# SparkFun_Transparent_Graphical_OLED_Brea.net
KiCad netlist of a schematic drawn in EAGLE
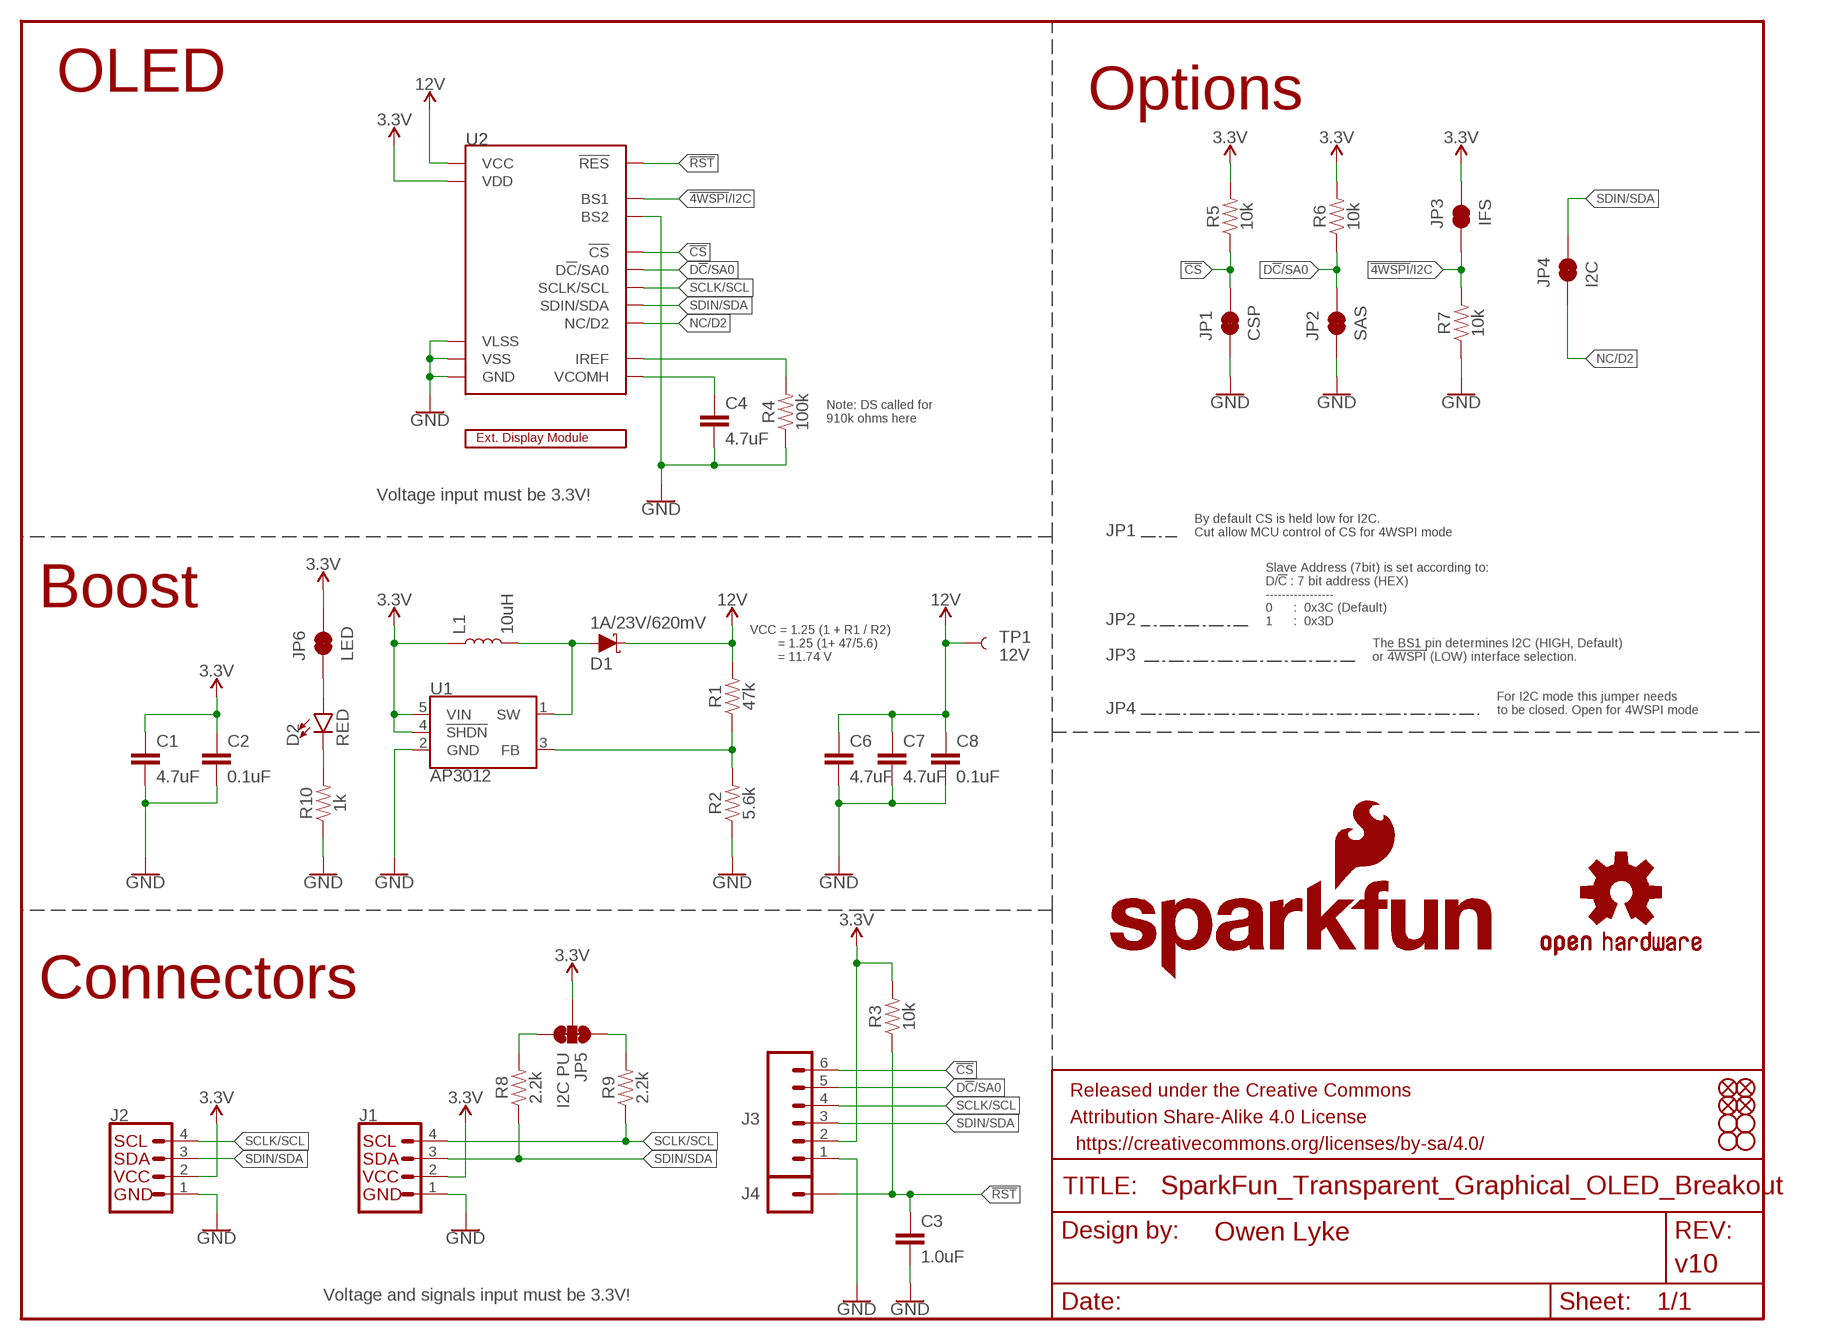
[diagram p0: schematic, sheet 1]

(export (version "E")
  (design (tool "Eeschema 10.0.6"))
  (components
    (comp (ref "C1")
      (value "4.7uF")
      (footprint "eagle-import:0603")
      (libsource (lib "eagle-import") (part "4.7UF-0603-35V-(20%)"))
    )
    (comp (ref "C2")
      (value "0.1uF")
      (footprint "eagle-import:0603")
      (libsource (lib "eagle-import") (part "0.1UF-0603-100V-10%"))
    )
    (comp (ref "C3")
      (value "1.0uF")
      (footprint "eagle-import:0603")
      (libsource (lib "eagle-import") (part "1.0UF-0603-16V-10%-X7R"))
    )
    (comp (ref "C4")
      (value "4.7uF")
      (footprint "eagle-import:0603")
      (libsource (lib "eagle-import") (part "4.7UF-0603-35V-(20%)"))
    )
    (comp (ref "C6")
      (value "4.7uF")
      (footprint "eagle-import:0603")
      (libsource (lib "eagle-import") (part "4.7UF-0603-35V-(20%)"))
    )
    (comp (ref "C7")
      (value "4.7uF")
      (footprint "eagle-import:0603")
      (libsource (lib "eagle-import") (part "4.7UF-0603-35V-(20%)"))
    )
    (comp (ref "C8")
      (value "0.1uF")
      (footprint "eagle-import:0603")
      (libsource (lib "eagle-import") (part "0.1UF-0603-100V-10%"))
    )
    (comp (ref "D1")
      (value "1A/23V/620mV")
      (footprint "eagle-import:SOD-323")
      (libsource (lib "eagle-import") (part "DIODE-SCHOTTKY-BAT20J"))
    )
    (comp (ref "D2")
      (value "RED")
      (footprint "eagle-import:LED-0603")
      (libsource (lib "eagle-import") (part "LED-RED0603"))
    )
    (comp (ref "FD1")
      (value "FIDUCIAL1X2")
      (footprint "eagle-import:FIDUCIAL-1X2")
      (libsource (lib "eagle-import") (part "FIDUCIAL1X2"))
    )
    (comp (ref "FD2")
      (value "FIDUCIAL1X2")
      (footprint "eagle-import:FIDUCIAL-1X2")
      (libsource (lib "eagle-import") (part "FIDUCIAL1X2"))
    )
    (comp (ref "FD3")
      (value "FIDUCIAL1X2")
      (footprint "eagle-import:FIDUCIAL-1X2")
      (libsource (lib "eagle-import") (part "FIDUCIAL1X2"))
    )
    (comp (ref "FD4")
      (value "FIDUCIAL1X2")
      (footprint "eagle-import:FIDUCIAL-1X2")
      (libsource (lib "eagle-import") (part "FIDUCIAL1X2"))
    )
    (comp (ref "FRAME1")
      (value "FRAME-LETTER")
      (footprint "eagle-import:CREATIVE_COMMONS")
      (fields (field (name "DESIGNER") "Owen Lyke") (field (name "REV") "v10"))
      (libsource (lib "eagle-import") (part "FRAME-LETTER"))
    )
    (comp (ref "H1")
      (value "STAND-OFF")
      (footprint "eagle-import:STAND-OFF")
      (libsource (lib "eagle-import") (part "STAND-OFF"))
    )
    (comp (ref "H2")
      (value "STAND-OFF")
      (footprint "eagle-import:STAND-OFF")
      (libsource (lib "eagle-import") (part "STAND-OFF"))
    )
    (comp (ref "H3")
      (value "STAND-OFF")
      (footprint "eagle-import:STAND-OFF")
      (libsource (lib "eagle-import") (part "STAND-OFF"))
    )
    (comp (ref "H4")
      (value "STAND-OFF")
      (footprint "eagle-import:STAND-OFF")
      (libsource (lib "eagle-import") (part "STAND-OFF"))
    )
    (comp (ref "J1")
      (value "QWIIC_CONNECTORJS-1MM")
      (footprint "eagle-import:JST04_1MM_RA")
      (libsource (lib "eagle-import") (part "QWIIC_CONNECTORJS-1MM"))
    )
    (comp (ref "J2")
      (value "QWIIC_CONNECTORJS-1MM")
      (footprint "eagle-import:JST04_1MM_RA")
      (libsource (lib "eagle-import") (part "QWIIC_CONNECTORJS-1MM"))
    )
    (comp (ref "J3")
      (value "CONN_06NO_SILK_NO_POP")
      (footprint "eagle-import:1X06_NO_SILK")
      (libsource (lib "eagle-import") (part "CONN_06NO_SILK_NO_POP"))
    )
    (comp (ref "J4")
      (value "CONN_01PTH_NO_SILK_YES_STOP")
      (footprint "eagle-import:1X01_NO_SILK")
      (libsource (lib "eagle-import") (part "CONN_01PTH_NO_SILK_YES_STOP"))
    )
    (comp (ref "JP1")
      (value "CSP")
      (footprint "eagle-import:SMT-JUMPER_2_NC_TRACE_SILK")
      (libsource (lib "eagle-import") (part "JUMPER-SMT_2_NC_TRACE_SILK"))
    )
    (comp (ref "JP2")
      (value "SAS")
      (footprint "eagle-import:SMT-JUMPER_2_NC_TRACE_SILK")
      (libsource (lib "eagle-import") (part "JUMPER-SMT_2_NC_TRACE_SILK"))
    )
    (comp (ref "JP3")
      (value "IFS")
      (footprint "eagle-import:SMT-JUMPER_2_NC_TRACE_SILK")
      (libsource (lib "eagle-import") (part "JUMPER-SMT_2_NC_TRACE_SILK"))
    )
    (comp (ref "JP4")
      (value "I2C")
      (footprint "eagle-import:SMT-JUMPER_2_NC_TRACE_SILK")
      (libsource (lib "eagle-import") (part "JUMPER-SMT_2_NC_TRACE_SILK"))
    )
    (comp (ref "JP5")
      (value "I2C PU")
      (footprint "eagle-import:SMT-JUMPER_3_2-NC_TRACE_SILK")
      (libsource (lib "eagle-import") (part "JUMPER-SMT_3_2-NC_TRACE_SILK"))
    )
    (comp (ref "JP6")
      (value "LED")
      (footprint "eagle-import:SMT-JUMPER_2_NC_TRACE_SILK")
      (libsource (lib "eagle-import") (part "JUMPER-SMT_2_NC_TRACE_SILK"))
    )
    (comp (ref "L1")
      (value "10uH")
      (footprint "eagle-import:INDUCTOR_4.7UH")
      (libsource (lib "eagle-import") (part "INDUCTOR-CDRH-10UH"))
    )
    (comp (ref "LOGO1")
      (value "SFE_LOGO_NAME_FLAME.1_INCH")
      (footprint "eagle-import:SFE_LOGO_NAME_FLAME_.1")
      (libsource (lib "eagle-import") (part "SFE_LOGO_NAME_FLAME.1_INCH"))
    )
    (comp (ref "LOGO2")
      (value "OSHW-LOGOS")
      (footprint "eagle-import:OSHW-LOGO-S")
      (libsource (lib "eagle-import") (part "OSHW-LOGOS"))
    )
    (comp (ref "R1")
      (value "47k")
      (footprint "eagle-import:0603")
      (libsource (lib "eagle-import") (part "47KOHM-0603-1/10W-1%"))
    )
    (comp (ref "R2")
      (value "5.6k")
      (footprint "eagle-import:0603")
      (libsource (lib "eagle-import") (part "5.6KOHM-0603-1/10W-1%"))
    )
    (comp (ref "R3")
      (value "10k")
      (footprint "eagle-import:0603")
      (libsource (lib "eagle-import") (part "10KOHM-0603-1/10W-1%"))
    )
    (comp (ref "R4")
      (value "100k")
      (footprint "eagle-import:0603")
      (libsource (lib "eagle-import") (part "100KOHM-0603-1/10W-1%"))
    )
    (comp (ref "R5")
      (value "10k")
      (footprint "eagle-import:0603")
      (libsource (lib "eagle-import") (part "10KOHM-0603-1/10W-1%"))
    )
    (comp (ref "R6")
      (value "10k")
      (footprint "eagle-import:0603")
      (libsource (lib "eagle-import") (part "10KOHM-0603-1/10W-1%"))
    )
    (comp (ref "R7")
      (value "10k")
      (footprint "eagle-import:0603")
      (libsource (lib "eagle-import") (part "10KOHM-0603-1/10W-1%"))
    )
    (comp (ref "R8")
      (value "2.2k")
      (footprint "eagle-import:0603")
      (libsource (lib "eagle-import") (part "2.2KOHM-0603-1/10W-1%"))
    )
    (comp (ref "R9")
      (value "2.2k")
      (footprint "eagle-import:0603")
      (libsource (lib "eagle-import") (part "2.2KOHM-0603-1/10W-1%"))
    )
    (comp (ref "R10")
      (value "1k")
      (footprint "eagle-import:0603")
      (libsource (lib "eagle-import") (part "1KOHM-0603-1/10W-1%"))
    )
    (comp (ref "TP1")
      (value "12V")
      (footprint "eagle-import:PAD.03X.03")
      (libsource (lib "eagle-import") (part "TEST-POINT3"))
    )
    (comp (ref "U$26")
      (value "EXTERNAL_DISP-UG-2856KLBAG01")
      (footprint "eagle-import:EXT_DISP")
      (libsource (lib "eagle-import") (part "EXTERNAL_DISP-UG-2856KLBAG01"))
    )
    (comp (ref "U1")
      (value "AP3012")
      (footprint "eagle-import:SOT23-5")
      (libsource (lib "eagle-import") (part "AP3012"))
    )
    (comp (ref "U2")
      (value "UG-2856KLBAG01_4WSPI")
      (footprint "eagle-import:FPC05024-42201")
      (libsource (lib "eagle-import") (part "UG-2856KLBAG01_4WSPI"))
    )
  )
  (nets
    (net (code "1") (name "/D~{C}{slash}SA0") (class "Default")
      (node (ref "J3") (pin "5") (pinfunction "5_5") (pintype "passive"))
      (node (ref "JP2") (pin "2") (pinfunction "2_2") (pintype "passive"))
      (node (ref "R6") (pin "1") (pinfunction "1_1") (pintype "passive"))
      (node (ref "U2") (pin "P$10") (pinfunction "D~{C}/SA0_P$10") (pintype "bidirectional"))
    )
    (net (code "2") (name "/~{4WSPI}{slash}I2C") (class "Default")
      (node (ref "JP3") (pin "2") (pinfunction "2_2") (pintype "passive"))
      (node (ref "R7") (pin "2") (pinfunction "2_2") (pintype "passive"))
      (node (ref "U2") (pin "P$6") (pinfunction "BS1_P$6") (pintype "bidirectional"))
    )
    (net (code "3") (name "/~{CS}") (class "Default")
      (node (ref "J3") (pin "6") (pinfunction "6_6") (pintype "passive"))
      (node (ref "JP1") (pin "2") (pinfunction "2_2") (pintype "passive"))
      (node (ref "R5") (pin "1") (pinfunction "1_1") (pintype "passive"))
      (node (ref "U2") (pin "P$8") (pinfunction "~{CS}_P$8") (pintype "bidirectional"))
    )
    (net (code "4") (name "/~{RST}") (class "Default")
      (node (ref "C3") (pin "1") (pinfunction "1_1") (pintype "passive"))
      (node (ref "J4") (pin "1") (pinfunction "1_1") (pintype "passive"))
      (node (ref "R3") (pin "1") (pinfunction "1_1") (pintype "passive"))
      (node (ref "U2") (pin "P$9") (pinfunction "~{RES}_P$9") (pintype "bidirectional"))
    )
    (net (code "5") (name "3.3V") (class "Default")
      (node (ref "C1") (pin "1") (pinfunction "1_1") (pintype "passive"))
      (node (ref "C2") (pin "1") (pinfunction "1_1") (pintype "passive"))
      (node (ref "J1") (pin "2") (pinfunction "2_2") (pintype "power_in"))
      (node (ref "J2") (pin "2") (pinfunction "2_2") (pintype "power_in"))
      (node (ref "J3") (pin "2") (pinfunction "2_2") (pintype "passive"))
      (node (ref "JP3") (pin "1") (pinfunction "1_1") (pintype "passive"))
      (node (ref "JP5") (pin "2") (pinfunction "2_2") (pintype "passive"))
      (node (ref "JP6") (pin "2") (pinfunction "2_2") (pintype "passive"))
      (node (ref "L1") (pin "P$1") (pinfunction "1_P$1") (pintype "passive"))
      (node (ref "R3") (pin "2") (pinfunction "2_2") (pintype "passive"))
      (node (ref "R5") (pin "2") (pinfunction "2_2") (pintype "passive"))
      (node (ref "R6") (pin "2") (pinfunction "2_2") (pintype "passive"))
      (node (ref "U1") (pin "4") (pinfunction "~{SHDN}_4") (pintype "bidirectional"))
      (node (ref "U1") (pin "5") (pinfunction "VIN_5") (pintype "bidirectional"))
      (node (ref "U2") (pin "P$5") (pinfunction "VDD_P$5") (pintype "bidirectional"))
    )
    (net (code "6") (name "12V") (class "Default")
      (node (ref "C6") (pin "1") (pinfunction "1_1") (pintype "passive"))
      (node (ref "C7") (pin "1") (pinfunction "1_1") (pintype "passive"))
      (node (ref "C8") (pin "1") (pinfunction "1_1") (pintype "passive"))
      (node (ref "D1") (pin "C") (pinfunction "C_C") (pintype "passive"))
      (node (ref "R1") (pin "2") (pinfunction "2_2") (pintype "passive"))
      (node (ref "TP1") (pin "P$1") (pinfunction "1_P$1") (pintype "bidirectional"))
      (node (ref "U2") (pin "P$23") (pinfunction "VCC_P$23") (pintype "bidirectional"))
    )
    (net (code "7") (name "GND") (class "Default")
      (node (ref "C1") (pin "2") (pinfunction "2_2") (pintype "passive"))
      (node (ref "C2") (pin "2") (pinfunction "2_2") (pintype "passive"))
      (node (ref "C3") (pin "2") (pinfunction "2_2") (pintype "passive"))
      (node (ref "C4") (pin "2") (pinfunction "2_2") (pintype "passive"))
      (node (ref "C6") (pin "2") (pinfunction "2_2") (pintype "passive"))
      (node (ref "C7") (pin "2") (pinfunction "2_2") (pintype "passive"))
      (node (ref "C8") (pin "2") (pinfunction "2_2") (pintype "passive"))
      (node (ref "J1") (pin "1") (pinfunction "1_1") (pintype "power_in"))
      (node (ref "J2") (pin "1") (pinfunction "1_1") (pintype "power_in"))
      (node (ref "J3") (pin "1") (pinfunction "1_1") (pintype "passive"))
      (node (ref "JP1") (pin "1") (pinfunction "1_1") (pintype "passive"))
      (node (ref "JP2") (pin "1") (pinfunction "1_1") (pintype "passive"))
      (node (ref "R10") (pin "1") (pinfunction "1_1") (pintype "passive"))
      (node (ref "R2") (pin "1") (pinfunction "1_1") (pintype "passive"))
      (node (ref "R4") (pin "1") (pinfunction "1_1") (pintype "passive"))
      (node (ref "R7") (pin "1") (pinfunction "1_1") (pintype "passive"))
      (node (ref "U1") (pin "2") (pinfunction "GND_2") (pintype "bidirectional"))
      (node (ref "U2") (pin "P$1") (pinfunction "GND_P$1") (pintype "bidirectional"))
      (node (ref "U2") (pin "P$11") (pinfunction "GND_P$11") (pintype "bidirectional"))
      (node (ref "U2") (pin "P$12") (pinfunction "GND_P$12") (pintype "bidirectional"))
      (node (ref "U2") (pin "P$16") (pinfunction "GND_P$16") (pintype "bidirectional"))
      (node (ref "U2") (pin "P$17") (pinfunction "GND_P$17") (pintype "bidirectional"))
      (node (ref "U2") (pin "P$18") (pinfunction "GND_P$18") (pintype "bidirectional"))
      (node (ref "U2") (pin "P$19") (pinfunction "GND_P$19") (pintype "bidirectional"))
      (node (ref "U2") (pin "P$2") (pinfunction "VLSS_P$2") (pintype "bidirectional"))
      (node (ref "U2") (pin "P$20") (pinfunction "GND_P$20") (pintype "bidirectional"))
      (node (ref "U2") (pin "P$24") (pinfunction "GND_P$24") (pintype "bidirectional"))
      (node (ref "U2") (pin "P$3") (pinfunction "VSS_P$3") (pintype "bidirectional"))
      (node (ref "U2") (pin "P$7") (pinfunction "BS2_P$7") (pintype "bidirectional"))
    )
    (net (code "8") (name "NC{slash}D2") (class "Default")
      (node (ref "JP4") (pin "1") (pinfunction "1_1") (pintype "passive"))
      (node (ref "U2") (pin "P$15") (pinfunction "NC/D2_P$15") (pintype "bidirectional"))
    )
    (net (code "9") (name "Net-(D2-PadA)") (class "Default")
      (node (ref "D2") (pin "A") (pinfunction "A_A") (pintype "passive"))
      (node (ref "JP6") (pin "1") (pinfunction "1_1") (pintype "passive"))
    )
    (net (code "10") (name "Net-(D2-PadC)") (class "Default")
      (node (ref "D2") (pin "C") (pinfunction "C_C") (pintype "passive"))
      (node (ref "R10") (pin "2") (pinfunction "2_2") (pintype "passive"))
    )
    (net (code "11") (name "Net-(JP5-Pad1)") (class "Default")
      (node (ref "JP5") (pin "1") (pinfunction "1_1") (pintype "passive"))
      (node (ref "R9") (pin "2") (pinfunction "2_2") (pintype "passive"))
    )
    (net (code "12") (name "Net-(JP5-Pad3)") (class "Default")
      (node (ref "JP5") (pin "3") (pinfunction "3_3") (pintype "passive"))
      (node (ref "R8") (pin "2") (pinfunction "2_2") (pintype "passive"))
    )
    (net (code "13") (name "Net-(L1-2)") (class "Default")
      (node (ref "D1") (pin "A") (pinfunction "A_A") (pintype "passive"))
      (node (ref "L1") (pin "P$2") (pinfunction "2_P$2") (pintype "passive"))
      (node (ref "U1") (pin "1") (pinfunction "SW_1") (pintype "bidirectional"))
    )
    (net (code "14") (name "Net-(U1-FB)") (class "Default")
      (node (ref "R1") (pin "1") (pinfunction "1_1") (pintype "passive"))
      (node (ref "R2") (pin "2") (pinfunction "2_2") (pintype "passive"))
      (node (ref "U1") (pin "3") (pinfunction "FB_3") (pintype "bidirectional"))
    )
    (net (code "15") (name "Net-(U2-IREF)") (class "Default")
      (node (ref "R4") (pin "2") (pinfunction "2_2") (pintype "passive"))
      (node (ref "U2") (pin "P$21") (pinfunction "IREF_P$21") (pintype "bidirectional"))
    )
    (net (code "16") (name "Net-(U2-VCOMH)") (class "Default")
      (node (ref "C4") (pin "1") (pinfunction "1_1") (pintype "passive"))
      (node (ref "U2") (pin "P$22") (pinfunction "VCOMH_P$22") (pintype "bidirectional"))
    )
    (net (code "17") (name "SCLK{slash}SCL") (class "Default")
      (node (ref "J1") (pin "4") (pinfunction "4_4") (pintype "passive"))
      (node (ref "J2") (pin "4") (pinfunction "4_4") (pintype "passive"))
      (node (ref "J3") (pin "4") (pinfunction "4_4") (pintype "passive"))
      (node (ref "R9") (pin "1") (pinfunction "1_1") (pintype "passive"))
      (node (ref "U2") (pin "P$13") (pinfunction "SCLK/SCL_P$13") (pintype "bidirectional"))
    )
    (net (code "18") (name "SDIN{slash}SDA") (class "Default")
      (node (ref "J1") (pin "3") (pinfunction "3_3") (pintype "passive"))
      (node (ref "J2") (pin "3") (pinfunction "3_3") (pintype "passive"))
      (node (ref "J3") (pin "3") (pinfunction "3_3") (pintype "passive"))
      (node (ref "JP4") (pin "2") (pinfunction "2_2") (pintype "passive"))
      (node (ref "R8") (pin "1") (pinfunction "1_1") (pintype "passive"))
      (node (ref "U2") (pin "P$14") (pinfunction "SDIN/SDA_P$14") (pintype "bidirectional"))
    )
  )
)
